# THE_FIRST.net
KiCad netlist of a schematic drawn in Altium Designer
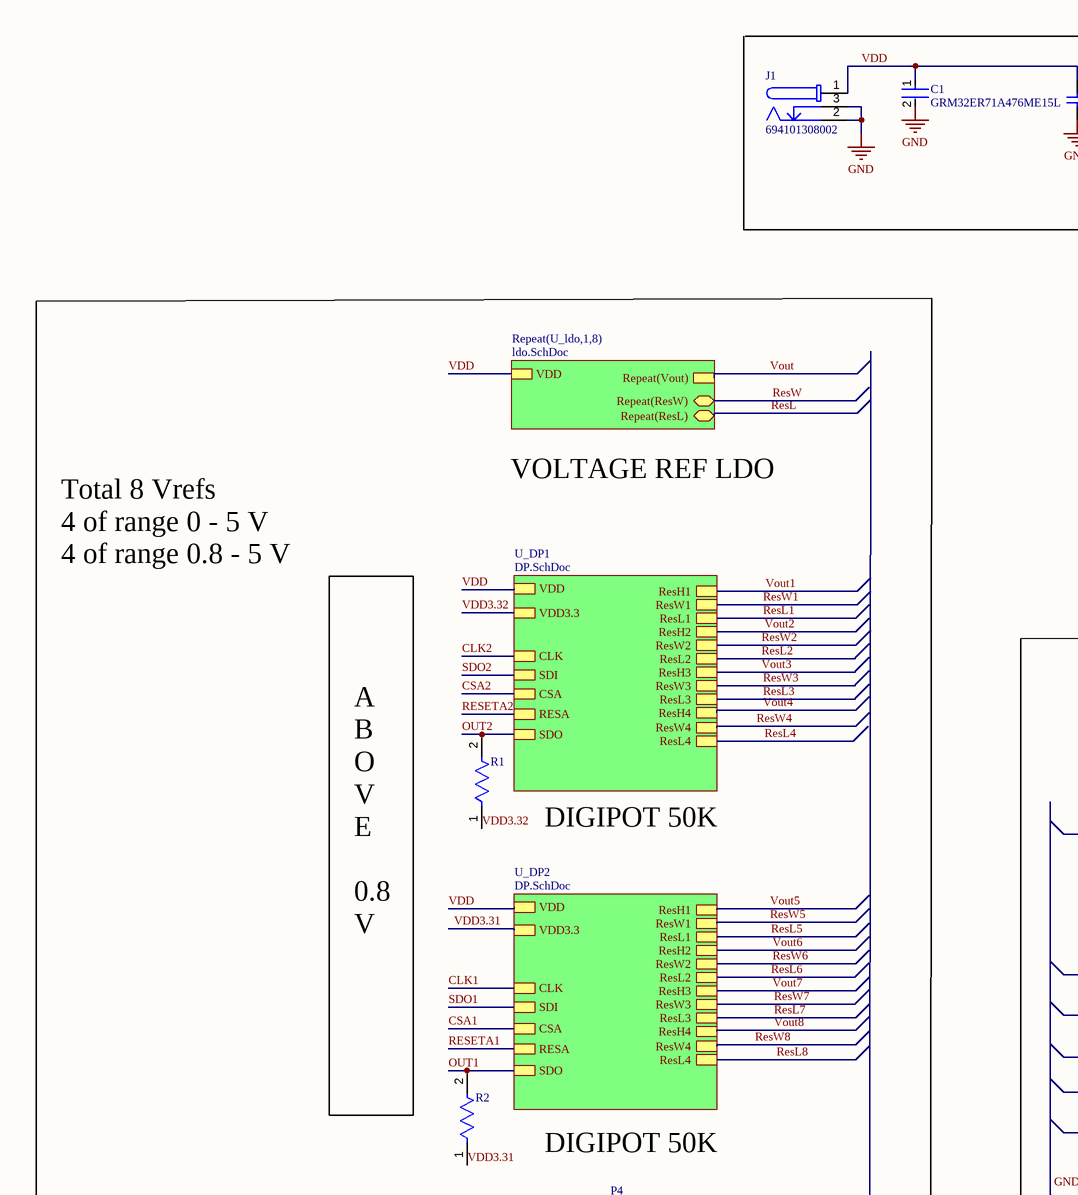
[diagram p0: THE_FIRST.SchDoc, top left]
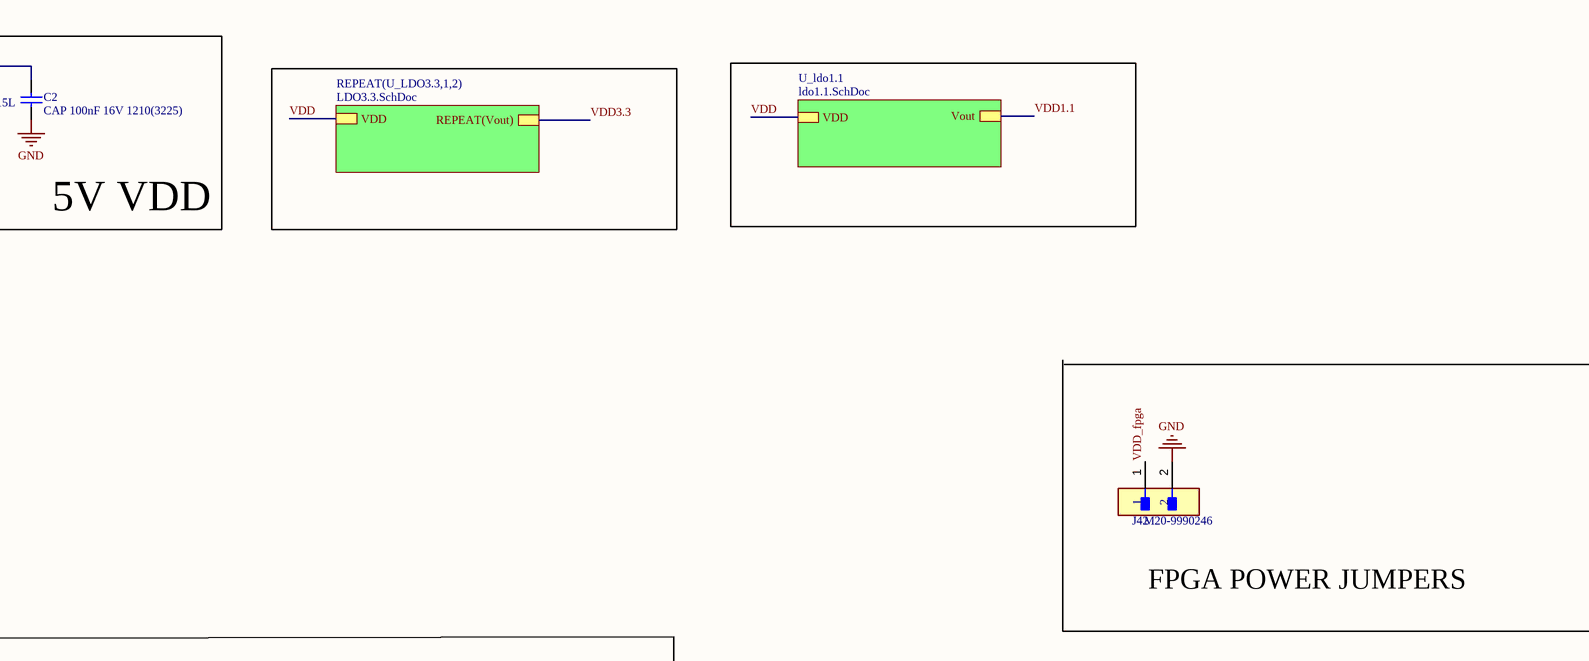
[diagram p1: THE_FIRST.SchDoc, top right]
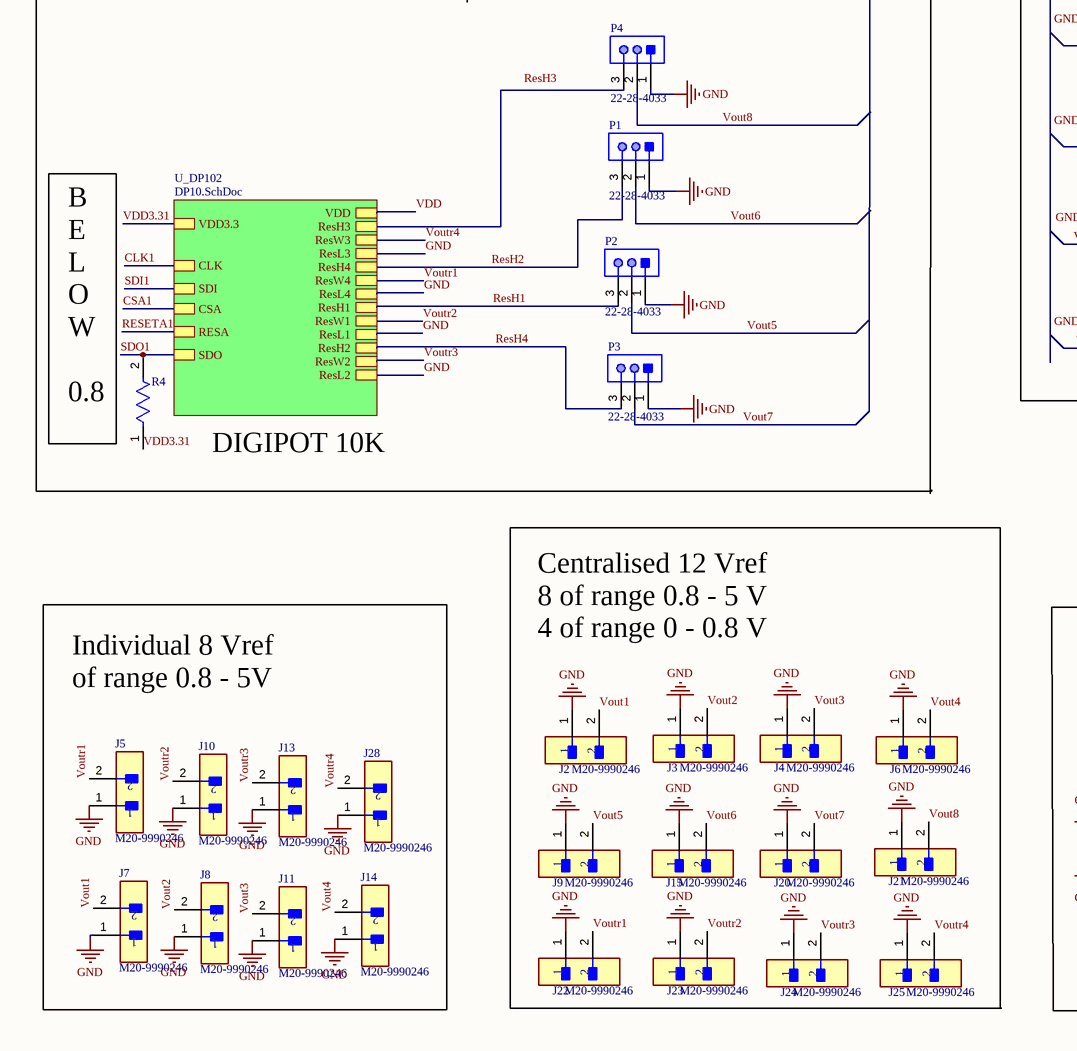
[diagram p2: THE_FIRST.SchDoc, bottom left]
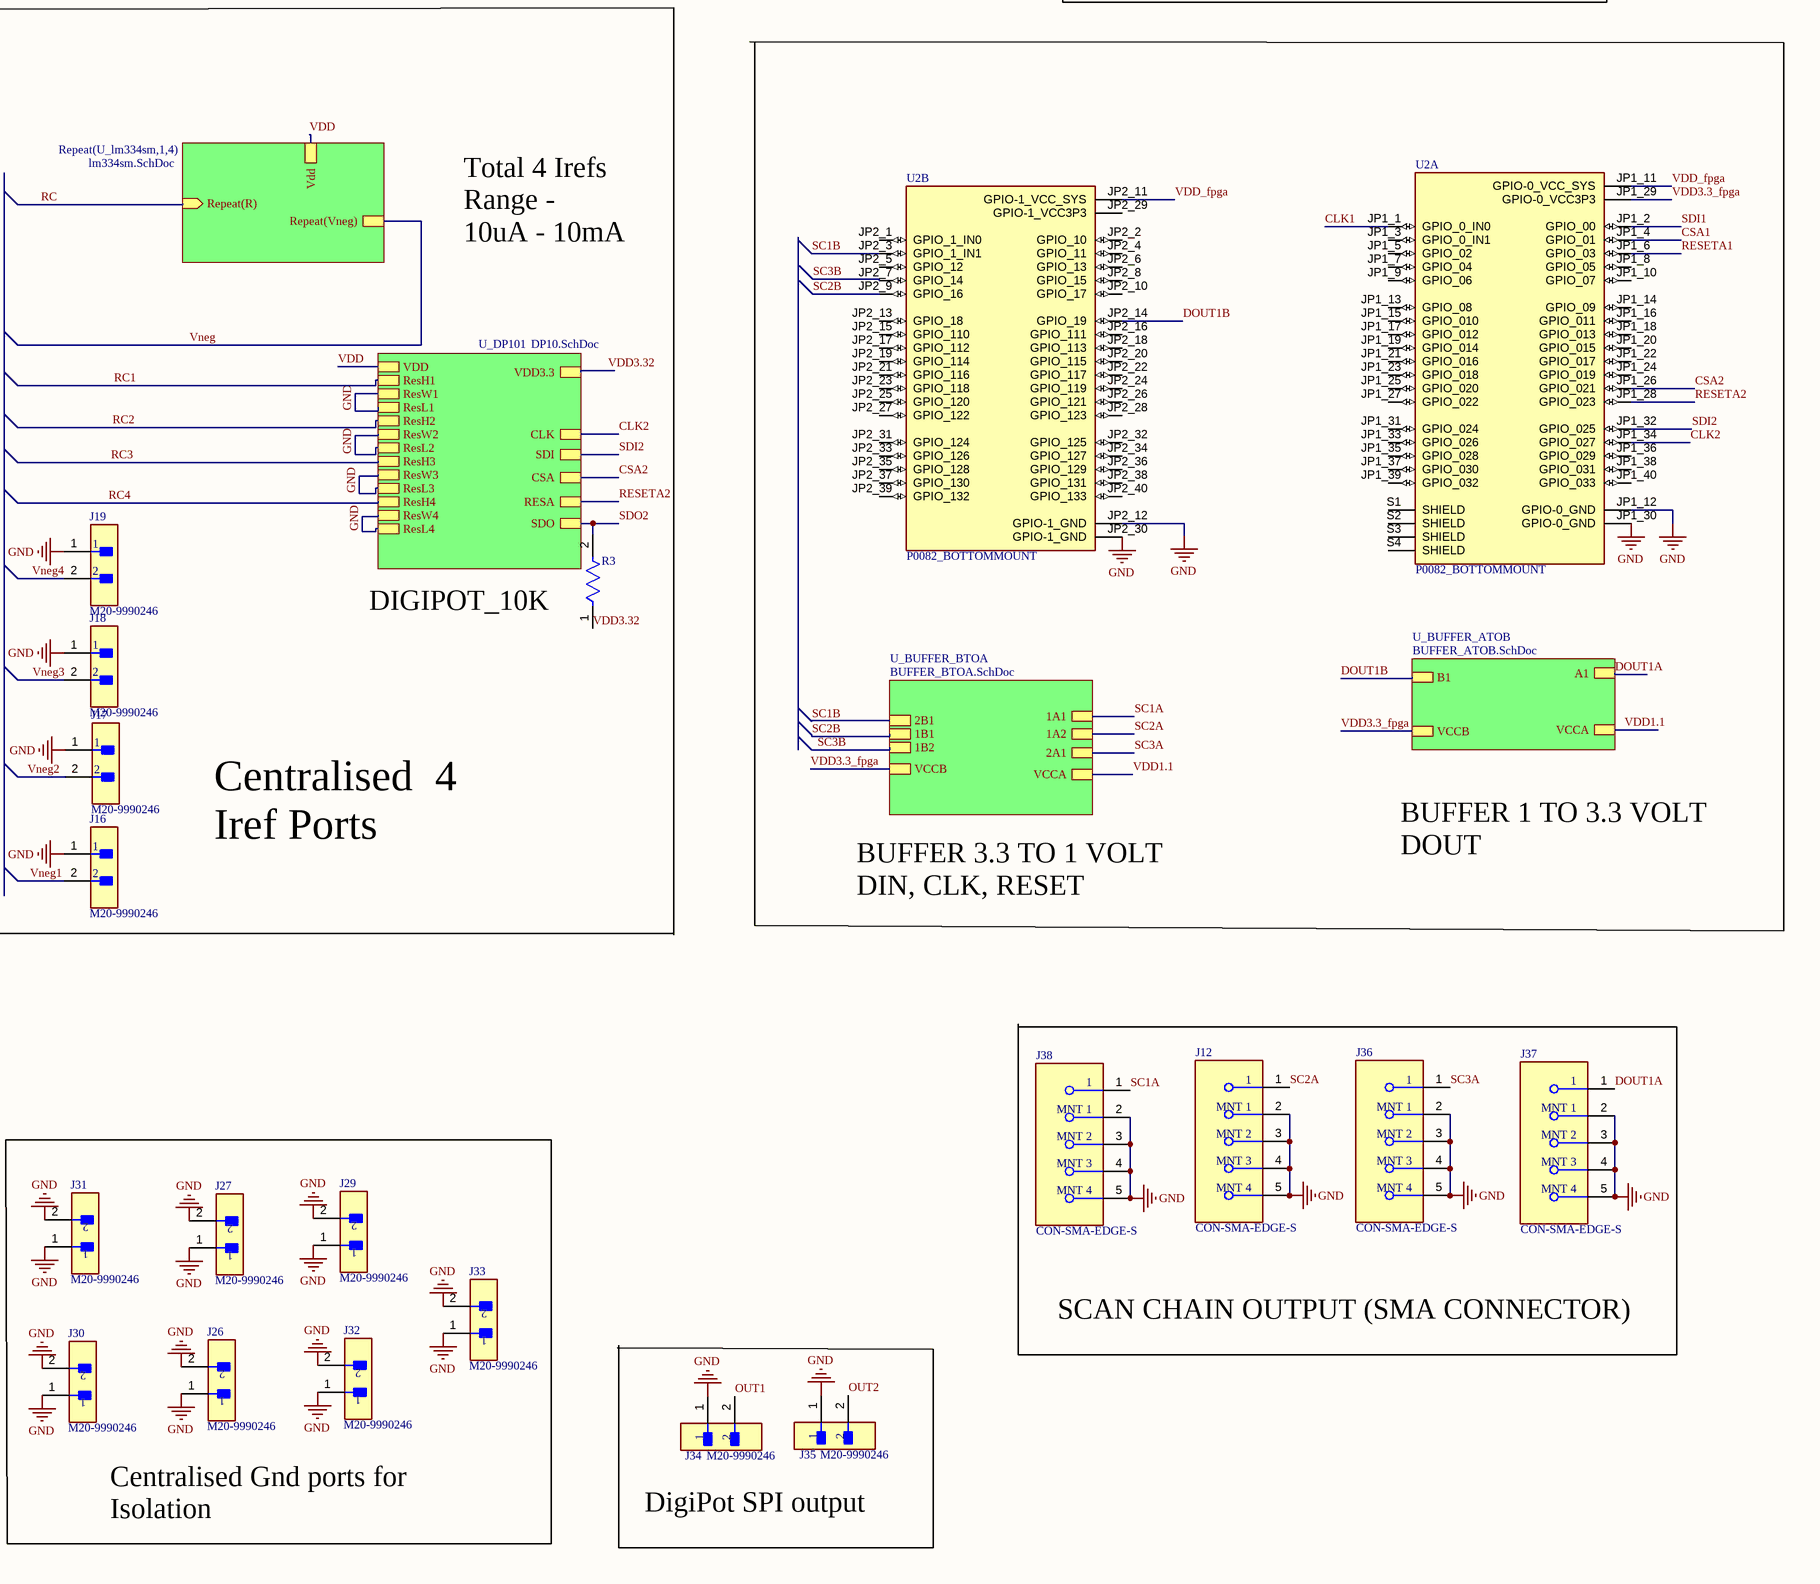
[diagram p3: THE_FIRST.SchDoc, bottom right]

(export (version "E")
  (design (tool "Eeschema 10.0.6"))
  (components
    (comp (ref "C1")
      (value "GRM32ER71A476ME15L")
      (footprint "FP-GRM32E-0_3-0_2-IPC_A")
      (description "Chip Multilayer Ceramic Capacitors for General Purpose, 1210, 47uF, X7R, 15%, 20%, 10V")
      (fields (field (name "VOLTAGE") "10V") (field (name "TOLERANCE") "20%"))
      (libsource (lib "Altium Content Vault") (part "02cd4be3c70576c341d710602a673aa"))
    )
    (comp (ref "C2")
      (value "CAP 100nF 16V 1210(3225)")
      (footprint "CAPC1210(3225)115_M")
      (description "CAP 100nF 16V ±1% 1210 (3225 Metric) Thickness 1.1mm SMD")
      (fields (field (name "TOLERANCE") "Â±1%") (field (name "MANUFACTURER") "Panasonic"))
      (libsource (lib "Altium Content Vault") (part "CAP"))
    )
    (comp (ref "J1")
      (value "694101308002")
      (footprint "694101308002")
      (libsource (lib "Altium Content Vault") (part "DC Power Jack"))
    )
    (comp (ref "J2")
      (value "M20-9990246")
      (footprint "FP-M20-9990246-MFG")
      (description "CONN HEADER VERT 2POS 2.54MM")
      (fields
        (field (name "OCTOPART") "https://octopart.com/m20-9990246-harwin-2590635")
        (field (name "MANUFACTURER") "Harwin")
      )
      (libsource (lib "Altium Content Vault") (part "3bc925449376181038e59eaffc5286c"))
    )
    (comp (ref "J3")
      (value "M20-9990246")
      (footprint "FP-M20-9990246-MFG")
      (description "CONN HEADER VERT 2POS 2.54MM")
      (fields
        (field (name "OCTOPART") "https://octopart.com/m20-9990246-harwin-2590635")
        (field (name "MANUFACTURER") "Harwin")
      )
      (libsource (lib "Altium Content Vault") (part "3bc925449376181038e59eaffc5286c"))
    )
    (comp (ref "J4")
      (value "M20-9990246")
      (footprint "FP-M20-9990246-MFG")
      (description "CONN HEADER VERT 2POS 2.54MM")
      (fields
        (field (name "OCTOPART") "https://octopart.com/m20-9990246-harwin-2590635")
        (field (name "MANUFACTURER") "Harwin")
      )
      (libsource (lib "Altium Content Vault") (part "3bc925449376181038e59eaffc5286c"))
    )
    (comp (ref "J5")
      (value "M20-9990246")
      (footprint "FP-M20-9990246-MFG")
      (description "CONN HEADER VERT 2POS 2.54MM")
      (fields
        (field (name "OCTOPART") "https://octopart.com/m20-9990246-harwin-2590635")
        (field (name "MANUFACTURER") "Harwin")
      )
      (libsource (lib "") (part "3bc925449376181038e59eaffc5286c_1"))
    )
    (comp (ref "J6")
      (value "M20-9990246")
      (footprint "FP-M20-9990246-MFG")
      (description "CONN HEADER VERT 2POS 2.54MM")
      (fields
        (field (name "OCTOPART") "https://octopart.com/m20-9990246-harwin-2590635")
        (field (name "MANUFACTURER") "Harwin")
      )
      (libsource (lib "Altium Content Vault") (part "3bc925449376181038e59eaffc5286c"))
    )
    (comp (ref "J7")
      (value "M20-9990246")
      (footprint "FP-M20-9990246-MFG")
      (description "CONN HEADER VERT 2POS 2.54MM")
      (fields
        (field (name "OCTOPART") "https://octopart.com/m20-9990246-harwin-2590635")
        (field (name "MANUFACTURER") "Harwin")
      )
      (libsource (lib "") (part "3bc925449376181038e59eaffc5286c_1"))
    )
    (comp (ref "J8")
      (value "M20-9990246")
      (footprint "FP-M20-9990246-MFG")
      (description "CONN HEADER VERT 2POS 2.54MM")
      (fields
        (field (name "OCTOPART") "https://octopart.com/m20-9990246-harwin-2590635")
        (field (name "MANUFACTURER") "Harwin")
      )
      (libsource (lib "") (part "3bc925449376181038e59eaffc5286c_1"))
    )
    (comp (ref "J9")
      (value "M20-9990246")
      (footprint "FP-M20-9990246-MFG")
      (description "CONN HEADER VERT 2POS 2.54MM")
      (fields
        (field (name "OCTOPART") "https://octopart.com/m20-9990246-harwin-2590635")
        (field (name "MANUFACTURER") "Harwin")
      )
      (libsource (lib "Altium Content Vault") (part "3bc925449376181038e59eaffc5286c"))
    )
    (comp (ref "J10")
      (value "M20-9990246")
      (footprint "FP-M20-9990246-MFG")
      (description "CONN HEADER VERT 2POS 2.54MM")
      (fields
        (field (name "OCTOPART") "https://octopart.com/m20-9990246-harwin-2590635")
        (field (name "MANUFACTURER") "Harwin")
      )
      (libsource (lib "") (part "3bc925449376181038e59eaffc5286c_1"))
    )
    (comp (ref "J11")
      (value "M20-9990246")
      (footprint "FP-M20-9990246-MFG")
      (description "CONN HEADER VERT 2POS 2.54MM")
      (fields
        (field (name "OCTOPART") "https://octopart.com/m20-9990246-harwin-2590635")
        (field (name "MANUFACTURER") "Harwin")
      )
      (libsource (lib "") (part "3bc925449376181038e59eaffc5286c_1"))
    )
    (comp (ref "J12")
      (value "CON-SMA-EDGE-S")
      (footprint "FP-CON-SMA-EDGE-S-MFG")
      (description "CONN SMA JACK STR EDGE MNT")
      (fields
        (field (name "OCTOPART") "https://octopart.com/con-sma-edge-s-rf+solutions-70967450")
        (field (name "MANUFACTURER") "RF Solutions Ltd.")
      )
      (libsource (lib "Altium Content Vault") (part "a163d97a771fcdd2fd1f1a9264c171f"))
    )
    (comp (ref "J13")
      (value "M20-9990246")
      (footprint "FP-M20-9990246-MFG")
      (description "CONN HEADER VERT 2POS 2.54MM")
      (fields
        (field (name "OCTOPART") "https://octopart.com/m20-9990246-harwin-2590635")
        (field (name "MANUFACTURER") "Harwin")
      )
      (libsource (lib "") (part "3bc925449376181038e59eaffc5286c_1"))
    )
    (comp (ref "J14")
      (value "M20-9990246")
      (footprint "FP-M20-9990246-MFG")
      (description "CONN HEADER VERT 2POS 2.54MM")
      (fields
        (field (name "OCTOPART") "https://octopart.com/m20-9990246-harwin-2590635")
        (field (name "MANUFACTURER") "Harwin")
      )
      (libsource (lib "") (part "3bc925449376181038e59eaffc5286c_1"))
    )
    (comp (ref "J15")
      (value "M20-9990246")
      (footprint "FP-M20-9990246-MFG")
      (description "CONN HEADER VERT 2POS 2.54MM")
      (fields
        (field (name "OCTOPART") "https://octopart.com/m20-9990246-harwin-2590635")
        (field (name "MANUFACTURER") "Harwin")
      )
      (libsource (lib "Altium Content Vault") (part "3bc925449376181038e59eaffc5286c"))
    )
    (comp (ref "J16")
      (value "M20-9990246")
      (footprint "FP-M20-9990246-MFG")
      (description "CONN HEADER VERT 2POS 2.54MM")
      (fields
        (field (name "OCTOPART") "https://octopart.com/m20-9990246-harwin-2590635")
        (field (name "MANUFACTURER") "Harwin")
      )
      (libsource (lib "") (part "3bc925449376181038e59eaffc5286c_2"))
    )
    (comp (ref "J17")
      (value "M20-9990246")
      (footprint "FP-M20-9990246-MFG")
      (description "CONN HEADER VERT 2POS 2.54MM")
      (fields
        (field (name "OCTOPART") "https://octopart.com/m20-9990246-harwin-2590635")
        (field (name "MANUFACTURER") "Harwin")
      )
      (libsource (lib "") (part "3bc925449376181038e59eaffc5286c_2"))
    )
    (comp (ref "J18")
      (value "M20-9990246")
      (footprint "FP-M20-9990246-MFG")
      (description "CONN HEADER VERT 2POS 2.54MM")
      (fields
        (field (name "OCTOPART") "https://octopart.com/m20-9990246-harwin-2590635")
        (field (name "MANUFACTURER") "Harwin")
      )
      (libsource (lib "") (part "3bc925449376181038e59eaffc5286c_2"))
    )
    (comp (ref "J19")
      (value "M20-9990246")
      (footprint "FP-M20-9990246-MFG")
      (description "CONN HEADER VERT 2POS 2.54MM")
      (fields
        (field (name "OCTOPART") "https://octopart.com/m20-9990246-harwin-2590635")
        (field (name "MANUFACTURER") "Harwin")
      )
      (libsource (lib "") (part "3bc925449376181038e59eaffc5286c_2"))
    )
    (comp (ref "J20")
      (value "M20-9990246")
      (footprint "FP-M20-9990246-MFG")
      (description "CONN HEADER VERT 2POS 2.54MM")
      (fields
        (field (name "OCTOPART") "https://octopart.com/m20-9990246-harwin-2590635")
        (field (name "MANUFACTURER") "Harwin")
      )
      (libsource (lib "Altium Content Vault") (part "3bc925449376181038e59eaffc5286c"))
    )
    (comp (ref "J21")
      (value "M20-9990246")
      (footprint "FP-M20-9990246-MFG")
      (description "CONN HEADER VERT 2POS 2.54MM")
      (fields
        (field (name "OCTOPART") "https://octopart.com/m20-9990246-harwin-2590635")
        (field (name "MANUFACTURER") "Harwin")
      )
      (libsource (lib "Altium Content Vault") (part "3bc925449376181038e59eaffc5286c"))
    )
    (comp (ref "J22")
      (value "M20-9990246")
      (footprint "FP-M20-9990246-MFG")
      (description "CONN HEADER VERT 2POS 2.54MM")
      (fields
        (field (name "OCTOPART") "https://octopart.com/m20-9990246-harwin-2590635")
        (field (name "MANUFACTURER") "Harwin")
      )
      (libsource (lib "Altium Content Vault") (part "3bc925449376181038e59eaffc5286c"))
    )
    (comp (ref "J23")
      (value "M20-9990246")
      (footprint "FP-M20-9990246-MFG")
      (description "CONN HEADER VERT 2POS 2.54MM")
      (fields
        (field (name "OCTOPART") "https://octopart.com/m20-9990246-harwin-2590635")
        (field (name "MANUFACTURER") "Harwin")
      )
      (libsource (lib "Altium Content Vault") (part "3bc925449376181038e59eaffc5286c"))
    )
    (comp (ref "J24")
      (value "M20-9990246")
      (footprint "FP-M20-9990246-MFG")
      (description "CONN HEADER VERT 2POS 2.54MM")
      (fields
        (field (name "OCTOPART") "https://octopart.com/m20-9990246-harwin-2590635")
        (field (name "MANUFACTURER") "Harwin")
      )
      (libsource (lib "Altium Content Vault") (part "3bc925449376181038e59eaffc5286c"))
    )
    (comp (ref "J25")
      (value "M20-9990246")
      (footprint "FP-M20-9990246-MFG")
      (description "CONN HEADER VERT 2POS 2.54MM")
      (fields
        (field (name "OCTOPART") "https://octopart.com/m20-9990246-harwin-2590635")
        (field (name "MANUFACTURER") "Harwin")
      )
      (libsource (lib "Altium Content Vault") (part "3bc925449376181038e59eaffc5286c"))
    )
    (comp (ref "J26")
      (value "M20-9990246")
      (footprint "FP-M20-9990246-MFG")
      (description "CONN HEADER VERT 2POS 2.54MM")
      (fields
        (field (name "OCTOPART") "https://octopart.com/m20-9990246-harwin-2590635")
        (field (name "MANUFACTURER") "Harwin")
      )
      (libsource (lib "") (part "3bc925449376181038e59eaffc5286c_1"))
    )
    (comp (ref "J27")
      (value "M20-9990246")
      (footprint "FP-M20-9990246-MFG")
      (description "CONN HEADER VERT 2POS 2.54MM")
      (fields
        (field (name "OCTOPART") "https://octopart.com/m20-9990246-harwin-2590635")
        (field (name "MANUFACTURER") "Harwin")
      )
      (libsource (lib "") (part "3bc925449376181038e59eaffc5286c_1"))
    )
    (comp (ref "J28")
      (value "M20-9990246")
      (footprint "FP-M20-9990246-MFG")
      (description "CONN HEADER VERT 2POS 2.54MM")
      (fields
        (field (name "OCTOPART") "https://octopart.com/m20-9990246-harwin-2590635")
        (field (name "MANUFACTURER") "Harwin")
      )
      (libsource (lib "") (part "3bc925449376181038e59eaffc5286c_1"))
    )
    (comp (ref "J29")
      (value "M20-9990246")
      (footprint "FP-M20-9990246-MFG")
      (description "CONN HEADER VERT 2POS 2.54MM")
      (fields
        (field (name "OCTOPART") "https://octopart.com/m20-9990246-harwin-2590635")
        (field (name "MANUFACTURER") "Harwin")
      )
      (libsource (lib "") (part "3bc925449376181038e59eaffc5286c_1"))
    )
    (comp (ref "J30")
      (value "M20-9990246")
      (footprint "FP-M20-9990246-MFG")
      (description "CONN HEADER VERT 2POS 2.54MM")
      (fields
        (field (name "OCTOPART") "https://octopart.com/m20-9990246-harwin-2590635")
        (field (name "MANUFACTURER") "Harwin")
      )
      (libsource (lib "") (part "3bc925449376181038e59eaffc5286c_1"))
    )
    (comp (ref "J31")
      (value "M20-9990246")
      (footprint "FP-M20-9990246-MFG")
      (description "CONN HEADER VERT 2POS 2.54MM")
      (fields
        (field (name "OCTOPART") "https://octopart.com/m20-9990246-harwin-2590635")
        (field (name "MANUFACTURER") "Harwin")
      )
      (libsource (lib "") (part "3bc925449376181038e59eaffc5286c_1"))
    )
    (comp (ref "J32")
      (value "M20-9990246")
      (footprint "FP-M20-9990246-MFG")
      (description "CONN HEADER VERT 2POS 2.54MM")
      (fields
        (field (name "OCTOPART") "https://octopart.com/m20-9990246-harwin-2590635")
        (field (name "MANUFACTURER") "Harwin")
      )
      (libsource (lib "") (part "3bc925449376181038e59eaffc5286c_1"))
    )
    (comp (ref "J33")
      (value "M20-9990246")
      (footprint "FP-M20-9990246-MFG")
      (description "CONN HEADER VERT 2POS 2.54MM")
      (fields
        (field (name "OCTOPART") "https://octopart.com/m20-9990246-harwin-2590635")
        (field (name "MANUFACTURER") "Harwin")
      )
      (libsource (lib "") (part "3bc925449376181038e59eaffc5286c_1"))
    )
    (comp (ref "J34")
      (value "M20-9990246")
      (footprint "FP-M20-9990246-MFG")
      (description "CONN HEADER VERT 2POS 2.54MM")
      (fields
        (field (name "OCTOPART") "https://octopart.com/m20-9990246-harwin-2590635")
        (field (name "MANUFACTURER") "Harwin")
      )
      (libsource (lib "Altium Content Vault") (part "3bc925449376181038e59eaffc5286c"))
    )
    (comp (ref "J35")
      (value "M20-9990246")
      (footprint "FP-M20-9990246-MFG")
      (description "CONN HEADER VERT 2POS 2.54MM")
      (fields
        (field (name "OCTOPART") "https://octopart.com/m20-9990246-harwin-2590635")
        (field (name "MANUFACTURER") "Harwin")
      )
      (libsource (lib "Altium Content Vault") (part "3bc925449376181038e59eaffc5286c"))
    )
    (comp (ref "J36")
      (value "CON-SMA-EDGE-S")
      (footprint "FP-CON-SMA-EDGE-S-MFG")
      (description "CONN SMA JACK STR EDGE MNT")
      (fields
        (field (name "OCTOPART") "https://octopart.com/con-sma-edge-s-rf+solutions-70967450")
        (field (name "MANUFACTURER") "RF Solutions Ltd.")
      )
      (libsource (lib "Altium Content Vault") (part "a163d97a771fcdd2fd1f1a9264c171f"))
    )
    (comp (ref "J37")
      (value "CON-SMA-EDGE-S")
      (footprint "FP-CON-SMA-EDGE-S-MFG")
      (description "CONN SMA JACK STR EDGE MNT")
      (fields
        (field (name "OCTOPART") "https://octopart.com/con-sma-edge-s-rf+solutions-70967450")
        (field (name "MANUFACTURER") "RF Solutions Ltd.")
      )
      (libsource (lib "Altium Content Vault") (part "a163d97a771fcdd2fd1f1a9264c171f"))
    )
    (comp (ref "J38")
      (value "CON-SMA-EDGE-S")
      (footprint "FP-CON-SMA-EDGE-S-MFG")
      (description "CONN SMA JACK STR EDGE MNT")
      (fields
        (field (name "OCTOPART") "https://octopart.com/con-sma-edge-s-rf+solutions-70967450")
        (field (name "MANUFACTURER") "RF Solutions Ltd.")
      )
      (libsource (lib "Altium Content Vault") (part "a163d97a771fcdd2fd1f1a9264c171f"))
    )
    (comp (ref "J42")
      (value "M20-9990246")
      (footprint "FP-M20-9990246-MFG")
      (description "CONN HEADER VERT 2POS 2.54MM")
      (fields
        (field (name "OCTOPART") "https://octopart.com/m20-9990246-harwin-2590635")
        (field (name "MANUFACTURER") "Harwin")
      )
      (libsource (lib "Altium Content Vault") (part "3bc925449376181038e59eaffc5286c"))
    )
    (comp (ref "P1")
      (value "22-28-4033")
      (footprint "MOLX-22-28-4033_V")
      (description "Male Header, Pitch 2.54 mm, 1 x 3 Position, Height 8.38 mm, Tail Length 3.18 mm, RoHS, Bulk")
      (fields (field (name "MANUFACTURER") "Molex"))
      (libsource (lib "Altium Content Vault") (part "CN-1P-M-R3"))
    )
    (comp (ref "P2")
      (value "22-28-4033")
      (footprint "MOLX-22-28-4033_V")
      (description "Male Header, Pitch 2.54 mm, 1 x 3 Position, Height 8.38 mm, Tail Length 3.18 mm, RoHS, Bulk")
      (fields (field (name "MANUFACTURER") "Molex"))
      (libsource (lib "Altium Content Vault") (part "CN-1P-M-R3"))
    )
    (comp (ref "P3")
      (value "22-28-4033")
      (footprint "MOLX-22-28-4033_V")
      (description "Male Header, Pitch 2.54 mm, 1 x 3 Position, Height 8.38 mm, Tail Length 3.18 mm, RoHS, Bulk")
      (fields (field (name "MANUFACTURER") "Molex"))
      (libsource (lib "Altium Content Vault") (part "CN-1P-M-R3"))
    )
    (comp (ref "P4")
      (value "22-28-4033")
      (footprint "MOLX-22-28-4033_V")
      (description "Male Header, Pitch 2.54 mm, 1 x 3 Position, Height 8.38 mm, Tail Length 3.18 mm, RoHS, Bulk")
      (fields (field (name "MANUFACTURER") "Molex"))
      (libsource (lib "Altium Content Vault") (part "CN-1P-M-R3"))
    )
    (comp (ref "R1")
      (value "ERA-2AEB222X")
      (footprint "FP-ERA2A-MFG")
      (description "RES SMD 2.2K OHM 0.1% 1/16W 0402")
      (fields
        (field (name "TOLERANCE") "0.1%")
        (field (name "OCTOPART") "https://octopart.com/era-2aeb222x-panasonic-9251391")
      )
      (libsource (lib "Altium Content Vault") (part "1029c3af85768c4190bb7ad29bc67b5"))
    )
    (comp (ref "R2")
      (value "ERA-2AEB222X")
      (footprint "FP-ERA2A-MFG")
      (description "RES SMD 2.2K OHM 0.1% 1/16W 0402")
      (fields
        (field (name "TOLERANCE") "0.1%")
        (field (name "OCTOPART") "https://octopart.com/era-2aeb222x-panasonic-9251391")
      )
      (libsource (lib "Altium Content Vault") (part "1029c3af85768c4190bb7ad29bc67b5"))
    )
    (comp (ref "R3")
      (value "ERA-2AEB222X")
      (footprint "FP-ERA2A-MFG")
      (description "RES SMD 2.2K OHM 0.1% 1/16W 0402")
      (fields
        (field (name "TOLERANCE") "0.1%")
        (field (name "OCTOPART") "https://octopart.com/era-2aeb222x-panasonic-9251391")
      )
      (libsource (lib "Altium Content Vault") (part "1029c3af85768c4190bb7ad29bc67b5"))
    )
    (comp (ref "R4")
      (value "ERA-2AEB222X")
      (footprint "FP-ERA2A-MFG")
      (description "RES SMD 2.2K OHM 0.1% 1/16W 0402")
      (fields
        (field (name "TOLERANCE") "0.1%")
        (field (name "OCTOPART") "https://octopart.com/era-2aeb222x-panasonic-9251391")
      )
      (libsource (lib "Altium Content Vault") (part "1029c3af85768c4190bb7ad29bc67b5"))
    )
    (comp (ref "U2")
      (value "P0082_BOTTOMMOUNT")
      (footprint "MODULE_P0082_BOTTOMMOUNT")
      (description "Cyclone IV E FPGA DE0-Nano EP4CE22 CycloneÂ® IV E FPGA Evaluation Board")
      (fields (field (name "MF") "Terasic Inc.") (field (name "MP") "P0082"))
      (libsource (lib "P0082_BOTTOMMOUNT") (part "P0082_BOTTOMMOUNT"))
    )
  )
  (nets
    (net (code "1") (name "/CLK1") (class "Default")
      (node (ref "U2") (pin "JP1_1") (pinfunction "GPIO_0_IN0_JP1_1") (pintype "bidirectional"))
    )
    (net (code "2") (name "/CLK2") (class "Default")
      (node (ref "U2") (pin "JP1_34") (pinfunction "GPIO_027_JP1_34") (pintype "bidirectional"))
    )
    (net (code "3") (name "/CSA1") (class "Default")
      (node (ref "U2") (pin "JP1_4") (pinfunction "GPIO_01_JP1_4") (pintype "bidirectional"))
    )
    (net (code "4") (name "/CSA2") (class "Default")
      (node (ref "U2") (pin "JP1_26") (pinfunction "GPIO_021_JP1_26") (pintype "bidirectional"))
    )
    (net (code "5") (name "/DOUT1A") (class "Default")
      (node (ref "J37") (pin "1") (pinfunction "1_1") (pintype "passive"))
    )
    (net (code "6") (name "/DOUT1B") (class "Default")
      (node (ref "U2") (pin "JP2_14") (pinfunction "GPIO_19_JP2_14") (pintype "bidirectional"))
    )
    (net (code "7") (name "/OUT1") (class "Default")
      (node (ref "J34") (pin "2") (pinfunction "2_2") (pintype "passive"))
      (node (ref "R2") (pin "2") (pinfunction "2_2") (pintype "passive"))
    )
    (net (code "8") (name "/OUT2") (class "Default")
      (node (ref "J35") (pin "2") (pinfunction "2_2") (pintype "passive"))
      (node (ref "R1") (pin "2") (pinfunction "2_2") (pintype "passive"))
    )
    (net (code "14") (name "/RESETA1") (class "Default")
      (node (ref "U2") (pin "JP1_6") (pinfunction "GPIO_03_JP1_6") (pintype "bidirectional"))
    )
    (net (code "15") (name "/RESETA2") (class "Default")
      (node (ref "U2") (pin "JP1_28") (pinfunction "GPIO_023_JP1_28") (pintype "bidirectional"))
    )
    (net (code "16") (name "/ResH1") (class "Default")
      (node (ref "P2") (pin "3") (pinfunction "3_3") (pintype "passive"))
    )
    (net (code "17") (name "/ResH2") (class "Default")
      (node (ref "P1") (pin "3") (pinfunction "3_3") (pintype "passive"))
    )
    (net (code "19") (name "/ResH3_1") (class "Default")
      (node (ref "P4") (pin "3") (pinfunction "3_3") (pintype "passive"))
    )
    (net (code "20") (name "/ResH4") (class "Default")
      (node (ref "P3") (pin "3") (pinfunction "3_3") (pintype "passive"))
    )
    (net (code "39") (name "/SC1A") (class "Default")
      (node (ref "J38") (pin "1") (pinfunction "1_1") (pintype "passive"))
    )
    (net (code "40") (name "/SC1B") (class "Default")
      (node (ref "U2") (pin "JP2_3") (pinfunction "GPIO_1_IN1_JP2_3") (pintype "bidirectional"))
    )
    (net (code "41") (name "/SC2A") (class "Default")
      (node (ref "J12") (pin "1") (pinfunction "1_1") (pintype "passive"))
    )
    (net (code "42") (name "/SC2B") (class "Default")
      (node (ref "U2") (pin "JP2_9") (pinfunction "GPIO_16_JP2_9") (pintype "bidirectional"))
    )
    (net (code "43") (name "/SC3A") (class "Default")
      (node (ref "J36") (pin "1") (pinfunction "1_1") (pintype "passive"))
    )
    (net (code "44") (name "/SC3B") (class "Default")
      (node (ref "U2") (pin "JP2_7") (pinfunction "GPIO_14_JP2_7") (pintype "bidirectional"))
    )
    (net (code "45") (name "/SDI1") (class "Default")
      (node (ref "U2") (pin "JP1_2") (pinfunction "GPIO_00_JP1_2") (pintype "bidirectional"))
    )
    (net (code "46") (name "/SDI2") (class "Default")
      (node (ref "U2") (pin "JP1_32") (pinfunction "GPIO_025_JP1_32") (pintype "bidirectional"))
    )
    (net (code "47") (name "/SDO1") (class "Default")
      (node (ref "R4") (pin "2") (pinfunction "2_2") (pintype "passive"))
    )
    (net (code "48") (name "/SDO2") (class "Default")
      (node (ref "R3") (pin "2") (pinfunction "2_2") (pintype "passive"))
    )
    (net (code "49") (name "/VDD") (class "Default")
      (node (ref "C1") (pin "1") (pinfunction "1_1") (pintype "passive"))
      (node (ref "C2") (pin "2") (pinfunction "2_2") (pintype "passive"))
      (node (ref "J1") (pin "1") (pinfunction "1_1") (pintype "passive"))
    )
    (net (code "52") (name "/VDD3.3_fpga") (class "Default")
      (node (ref "U2") (pin "JP1_29") (pinfunction "GPIO-0_VCC3P3_JP1_29") (pintype "power_in"))
    )
    (net (code "53") (name "/VDD3.31") (class "Default")
      (node (ref "R2") (pin "1") (pinfunction "1_1") (pintype "passive"))
      (node (ref "R4") (pin "1") (pinfunction "1_1") (pintype "passive"))
    )
    (net (code "54") (name "/VDD3.32") (class "Default")
      (node (ref "R1") (pin "1") (pinfunction "1_1") (pintype "passive"))
      (node (ref "R3") (pin "1") (pinfunction "1_1") (pintype "passive"))
    )
    (net (code "55") (name "/VDD_fpga") (class "Default")
      (node (ref "J42") (pin "1") (pinfunction "1_1") (pintype "passive"))
      (node (ref "U2") (pin "JP1_11") (pinfunction "GPIO-0_VCC_SYS_JP1_11") (pintype "power_in"))
      (node (ref "U2") (pin "JP2_11") (pinfunction "GPIO-1_VCC_SYS_JP2_11") (pintype "power_in"))
    )
    (net (code "57") (name "/Vneg1") (class "Default")
      (node (ref "J16") (pin "2") (pinfunction "2_2") (pintype "passive"))
    )
    (net (code "58") (name "/Vneg2") (class "Default")
      (node (ref "J17") (pin "2") (pinfunction "2_2") (pintype "passive"))
    )
    (net (code "59") (name "/Vneg3") (class "Default")
      (node (ref "J18") (pin "2") (pinfunction "2_2") (pintype "passive"))
    )
    (net (code "60") (name "/Vneg4") (class "Default")
      (node (ref "J19") (pin "2") (pinfunction "2_2") (pintype "passive"))
    )
    (net (code "62") (name "/Vout1") (class "Default")
      (node (ref "J2") (pin "2") (pinfunction "2_2") (pintype "passive"))
      (node (ref "J7") (pin "2") (pinfunction "2_2") (pintype "passive"))
    )
    (net (code "63") (name "/Vout2") (class "Default")
      (node (ref "J3") (pin "2") (pinfunction "2_2") (pintype "passive"))
      (node (ref "J8") (pin "2") (pinfunction "2_2") (pintype "passive"))
    )
    (net (code "64") (name "/Vout3") (class "Default")
      (node (ref "J11") (pin "2") (pinfunction "2_2") (pintype "passive"))
      (node (ref "J4") (pin "2") (pinfunction "2_2") (pintype "passive"))
    )
    (net (code "65") (name "/Vout4") (class "Default")
      (node (ref "J14") (pin "2") (pinfunction "2_2") (pintype "passive"))
      (node (ref "J6") (pin "2") (pinfunction "2_2") (pintype "passive"))
    )
    (net (code "66") (name "/Vout5") (class "Default")
      (node (ref "J9") (pin "2") (pinfunction "2_2") (pintype "passive"))
      (node (ref "P2") (pin "2") (pinfunction "2_2") (pintype "passive"))
    )
    (net (code "67") (name "/Vout6") (class "Default")
      (node (ref "J15") (pin "2") (pinfunction "2_2") (pintype "passive"))
      (node (ref "P1") (pin "2") (pinfunction "2_2") (pintype "passive"))
    )
    (net (code "68") (name "/Vout7") (class "Default")
      (node (ref "J20") (pin "2") (pinfunction "2_2") (pintype "passive"))
      (node (ref "P3") (pin "2") (pinfunction "2_2") (pintype "passive"))
    )
    (net (code "69") (name "/Vout8") (class "Default")
      (node (ref "J21") (pin "2") (pinfunction "2_2") (pintype "passive"))
      (node (ref "P4") (pin "2") (pinfunction "2_2") (pintype "passive"))
    )
    (net (code "70") (name "/Voutr1") (class "Default")
      (node (ref "J22") (pin "2") (pinfunction "2_2") (pintype "passive"))
      (node (ref "J5") (pin "2") (pinfunction "2_2") (pintype "passive"))
    )
    (net (code "71") (name "/Voutr2") (class "Default")
      (node (ref "J10") (pin "2") (pinfunction "2_2") (pintype "passive"))
      (node (ref "J23") (pin "2") (pinfunction "2_2") (pintype "passive"))
    )
    (net (code "72") (name "/Voutr3") (class "Default")
      (node (ref "J13") (pin "2") (pinfunction "2_2") (pintype "passive"))
      (node (ref "J24") (pin "2") (pinfunction "2_2") (pintype "passive"))
    )
    (net (code "73") (name "/Voutr4") (class "Default")
      (node (ref "J25") (pin "2") (pinfunction "2_2") (pintype "passive"))
      (node (ref "J28") (pin "2") (pinfunction "2_2") (pintype "passive"))
    )
    (net (code "74") (name "GND") (class "Default")
      (node (ref "C1") (pin "2") (pinfunction "2_2") (pintype "passive"))
      (node (ref "C2") (pin "1") (pinfunction "1_1") (pintype "passive"))
      (node (ref "J1") (pin "2") (pinfunction "2_2") (pintype "passive"))
      (node (ref "J1") (pin "3") (pinfunction "3_3") (pintype "passive"))
      (node (ref "J10") (pin "1") (pinfunction "1_1") (pintype "passive"))
      (node (ref "J11") (pin "1") (pinfunction "1_1") (pintype "passive"))
      (node (ref "J12") (pin "2") (pinfunction "MNT_1_2") (pintype "passive"))
      (node (ref "J12") (pin "3") (pinfunction "MNT_2_3") (pintype "passive"))
      (node (ref "J12") (pin "4") (pinfunction "MNT_3_4") (pintype "passive"))
      (node (ref "J12") (pin "5") (pinfunction "MNT_4_5") (pintype "passive"))
      (node (ref "J13") (pin "1") (pinfunction "1_1") (pintype "passive"))
      (node (ref "J14") (pin "1") (pinfunction "1_1") (pintype "passive"))
      (node (ref "J15") (pin "1") (pinfunction "1_1") (pintype "passive"))
      (node (ref "J16") (pin "1") (pinfunction "1_1") (pintype "passive"))
      (node (ref "J17") (pin "1") (pinfunction "1_1") (pintype "passive"))
      (node (ref "J18") (pin "1") (pinfunction "1_1") (pintype "passive"))
      (node (ref "J19") (pin "1") (pinfunction "1_1") (pintype "passive"))
      (node (ref "J2") (pin "1") (pinfunction "1_1") (pintype "passive"))
      (node (ref "J20") (pin "1") (pinfunction "1_1") (pintype "passive"))
      (node (ref "J21") (pin "1") (pinfunction "1_1") (pintype "passive"))
      (node (ref "J22") (pin "1") (pinfunction "1_1") (pintype "passive"))
      (node (ref "J23") (pin "1") (pinfunction "1_1") (pintype "passive"))
      (node (ref "J24") (pin "1") (pinfunction "1_1") (pintype "passive"))
      (node (ref "J25") (pin "1") (pinfunction "1_1") (pintype "passive"))
      (node (ref "J26") (pin "1") (pinfunction "1_1") (pintype "passive"))
      (node (ref "J26") (pin "2") (pinfunction "2_2") (pintype "passive"))
      (node (ref "J27") (pin "1") (pinfunction "1_1") (pintype "passive"))
      (node (ref "J27") (pin "2") (pinfunction "2_2") (pintype "passive"))
      (node (ref "J28") (pin "1") (pinfunction "1_1") (pintype "passive"))
      (node (ref "J29") (pin "1") (pinfunction "1_1") (pintype "passive"))
      (node (ref "J29") (pin "2") (pinfunction "2_2") (pintype "passive"))
      (node (ref "J3") (pin "1") (pinfunction "1_1") (pintype "passive"))
      (node (ref "J30") (pin "1") (pinfunction "1_1") (pintype "passive"))
      (node (ref "J30") (pin "2") (pinfunction "2_2") (pintype "passive"))
      (node (ref "J31") (pin "1") (pinfunction "1_1") (pintype "passive"))
      (node (ref "J31") (pin "2") (pinfunction "2_2") (pintype "passive"))
      (node (ref "J32") (pin "1") (pinfunction "1_1") (pintype "passive"))
      (node (ref "J32") (pin "2") (pinfunction "2_2") (pintype "passive"))
      (node (ref "J33") (pin "1") (pinfunction "1_1") (pintype "passive"))
      (node (ref "J33") (pin "2") (pinfunction "2_2") (pintype "passive"))
      (node (ref "J34") (pin "1") (pinfunction "1_1") (pintype "passive"))
      (node (ref "J35") (pin "1") (pinfunction "1_1") (pintype "passive"))
      (node (ref "J36") (pin "2") (pinfunction "MNT_1_2") (pintype "passive"))
      (node (ref "J36") (pin "3") (pinfunction "MNT_2_3") (pintype "passive"))
      (node (ref "J36") (pin "4") (pinfunction "MNT_3_4") (pintype "passive"))
      (node (ref "J36") (pin "5") (pinfunction "MNT_4_5") (pintype "passive"))
      (node (ref "J37") (pin "2") (pinfunction "MNT_1_2") (pintype "passive"))
      (node (ref "J37") (pin "3") (pinfunction "MNT_2_3") (pintype "passive"))
      (node (ref "J37") (pin "4") (pinfunction "MNT_3_4") (pintype "passive"))
      (node (ref "J37") (pin "5") (pinfunction "MNT_4_5") (pintype "passive"))
      (node (ref "J38") (pin "2") (pinfunction "MNT_1_2") (pintype "passive"))
      (node (ref "J38") (pin "3") (pinfunction "MNT_2_3") (pintype "passive"))
      (node (ref "J38") (pin "4") (pinfunction "MNT_3_4") (pintype "passive"))
      (node (ref "J38") (pin "5") (pinfunction "MNT_4_5") (pintype "passive"))
      (node (ref "J4") (pin "1") (pinfunction "1_1") (pintype "passive"))
      (node (ref "J42") (pin "2") (pinfunction "2_2") (pintype "passive"))
      (node (ref "J5") (pin "1") (pinfunction "1_1") (pintype "passive"))
      (node (ref "J6") (pin "1") (pinfunction "1_1") (pintype "passive"))
      (node (ref "J7") (pin "1") (pinfunction "1_1") (pintype "passive"))
      (node (ref "J8") (pin "1") (pinfunction "1_1") (pintype "passive"))
      (node (ref "J9") (pin "1") (pinfunction "1_1") (pintype "passive"))
      (node (ref "P1") (pin "1") (pinfunction "1_1") (pintype "passive"))
      (node (ref "P2") (pin "1") (pinfunction "1_1") (pintype "passive"))
      (node (ref "P3") (pin "1") (pinfunction "1_1") (pintype "passive"))
      (node (ref "P4") (pin "1") (pinfunction "1_1") (pintype "passive"))
      (node (ref "U2") (pin "JP1_12") (pinfunction "GPIO-0_GND_JP1_12") (pintype "power_in"))
      (node (ref "U2") (pin "JP1_30") (pinfunction "GPIO-0_GND_JP1_30") (pintype "power_in"))
      (node (ref "U2") (pin "JP2_12") (pinfunction "GPIO-1_GND_JP2_12") (pintype "power_in"))
      (node (ref "U2") (pin "JP2_30") (pinfunction "GPIO-1_GND_JP2_30") (pintype "power_in"))
    )
    (net (code "75") (name "unconnected-(U2A-GPIO_0_IN1-PadJP1_3)") (class "Default")
      (node (ref "U2") (pin "JP1_3") (pinfunction "GPIO_0_IN1_JP1_3") (pintype "bidirectional"))
    )
    (net (code "76") (name "unconnected-(U2A-GPIO_02-PadJP1_5)") (class "Default")
      (node (ref "U2") (pin "JP1_5") (pinfunction "GPIO_02_JP1_5") (pintype "bidirectional"))
    )
    (net (code "77") (name "unconnected-(U2A-GPIO_04-PadJP1_7)") (class "Default")
      (node (ref "U2") (pin "JP1_7") (pinfunction "GPIO_04_JP1_7") (pintype "bidirectional"))
    )
    (net (code "78") (name "unconnected-(U2A-GPIO_05-PadJP1_8)") (class "Default")
      (node (ref "U2") (pin "JP1_8") (pinfunction "GPIO_05_JP1_8") (pintype "bidirectional"))
    )
    (net (code "79") (name "unconnected-(U2A-GPIO_06-PadJP1_9)") (class "Default")
      (node (ref "U2") (pin "JP1_9") (pinfunction "GPIO_06_JP1_9") (pintype "bidirectional"))
    )
    (net (code "80") (name "unconnected-(U2A-GPIO_07-PadJP1_10)") (class "Default")
      (node (ref "U2") (pin "JP1_10") (pinfunction "GPIO_07_JP1_10") (pintype "bidirectional"))
    )
    (net (code "81") (name "unconnected-(U2A-GPIO_08-PadJP1_13)") (class "Default")
      (node (ref "U2") (pin "JP1_13") (pinfunction "GPIO_08_JP1_13") (pintype "bidirectional"))
    )
    (net (code "82") (name "unconnected-(U2A-GPIO_09-PadJP1_14)") (class "Default")
      (node (ref "U2") (pin "JP1_14") (pinfunction "GPIO_09_JP1_14") (pintype "bidirectional"))
    )
    (net (code "83") (name "unconnected-(U2A-GPIO_010-PadJP1_15)") (class "Default")
      (node (ref "U2") (pin "JP1_15") (pinfunction "GPIO_010_JP1_15") (pintype "bidirectional"))
    )
    (net (code "84") (name "unconnected-(U2A-GPIO_011-PadJP1_16)") (class "Default")
      (node (ref "U2") (pin "JP1_16") (pinfunction "GPIO_011_JP1_16") (pintype "bidirectional"))
    )
    (net (code "85") (name "unconnected-(U2A-GPIO_012-PadJP1_17)") (class "Default")
      (node (ref "U2") (pin "JP1_17") (pinfunction "GPIO_012_JP1_17") (pintype "bidirectional"))
    )
    (net (code "86") (name "unconnected-(U2A-GPIO_013-PadJP1_18)") (class "Default")
      (node (ref "U2") (pin "JP1_18") (pinfunction "GPIO_013_JP1_18") (pintype "bidirectional"))
    )
    (net (code "87") (name "unconnected-(U2A-GPIO_014-PadJP1_19)") (class "Default")
      (node (ref "U2") (pin "JP1_19") (pinfunction "GPIO_014_JP1_19") (pintype "bidirectional"))
    )
    (net (code "88") (name "unconnected-(U2A-GPIO_015-PadJP1_20)") (class "Default")
      (node (ref "U2") (pin "JP1_20") (pinfunction "GPIO_015_JP1_20") (pintype "bidirectional"))
    )
    (net (code "89") (name "unconnected-(U2A-GPIO_016-PadJP1_21)") (class "Default")
      (node (ref "U2") (pin "JP1_21") (pinfunction "GPIO_016_JP1_21") (pintype "bidirectional"))
    )
    (net (code "90") (name "unconnected-(U2A-GPIO_017-PadJP1_22)") (class "Default")
      (node (ref "U2") (pin "JP1_22") (pinfunction "GPIO_017_JP1_22") (pintype "bidirectional"))
    )
    (net (code "91") (name "unconnected-(U2A-GPIO_018-PadJP1_23)") (class "Default")
      (node (ref "U2") (pin "JP1_23") (pinfunction "GPIO_018_JP1_23") (pintype "bidirectional"))
    )
    (net (code "92") (name "unconnected-(U2A-GPIO_019-PadJP1_24)") (class "Default")
      (node (ref "U2") (pin "JP1_24") (pinfunction "GPIO_019_JP1_24") (pintype "bidirectional"))
    )
    (net (code "93") (name "unconnected-(U2A-GPIO_020-PadJP1_25)") (class "Default")
      (node (ref "U2") (pin "JP1_25") (pinfunction "GPIO_020_JP1_25") (pintype "bidirectional"))
    )
    (net (code "94") (name "unconnected-(U2A-GPIO_022-PadJP1_27)") (class "Default")
      (node (ref "U2") (pin "JP1_27") (pinfunction "GPIO_022_JP1_27") (pintype "bidirectional"))
    )
    (net (code "95") (name "unconnected-(U2A-GPIO_024-PadJP1_31)") (class "Default")
      (node (ref "U2") (pin "JP1_31") (pinfunction "GPIO_024_JP1_31") (pintype "bidirectional"))
    )
    (net (code "96") (name "unconnected-(U2A-GPIO_026-PadJP1_33)") (class "Default")
      (node (ref "U2") (pin "JP1_33") (pinfunction "GPIO_026_JP1_33") (pintype "bidirectional"))
    )
    (net (code "97") (name "unconnected-(U2A-GPIO_028-PadJP1_35)") (class "Default")
      (node (ref "U2") (pin "JP1_35") (pinfunction "GPIO_028_JP1_35") (pintype "bidirectional"))
    )
    (net (code "98") (name "unconnected-(U2A-GPIO_029-PadJP1_36)") (class "Default")
      (node (ref "U2") (pin "JP1_36") (pinfunction "GPIO_029_JP1_36") (pintype "bidirectional"))
    )
    (net (code "99") (name "unconnected-(U2A-GPIO_030-PadJP1_37)") (class "Default")
      (node (ref "U2") (pin "JP1_37") (pinfunction "GPIO_030_JP1_37") (pintype "bidirectional"))
    )
    (net (code "100") (name "unconnected-(U2A-GPIO_031-PadJP1_38)") (class "Default")
      (node (ref "U2") (pin "JP1_38") (pinfunction "GPIO_031_JP1_38") (pintype "bidirectional"))
    )
    (net (code "101") (name "unconnected-(U2A-GPIO_032-PadJP1_39)") (class "Default")
      (node (ref "U2") (pin "JP1_39") (pinfunction "GPIO_032_JP1_39") (pintype "bidirectional"))
    )
    (net (code "102") (name "unconnected-(U2A-GPIO_033-PadJP1_40)") (class "Default")
      (node (ref "U2") (pin "JP1_40") (pinfunction "GPIO_033_JP1_40") (pintype "bidirectional"))
    )
    (net (code "103") (name "unconnected-(U2A-SHIELD-PadS1)") (class "Default")
      (node (ref "U2") (pin "S1") (pinfunction "SHIELD_S1") (pintype "passive"))
    )
    (net (code "104") (name "unconnected-(U2A-SHIELD-PadS2)") (class "Default")
      (node (ref "U2") (pin "S2") (pinfunction "SHIELD_S2") (pintype "passive"))
    )
    (net (code "105") (name "unconnected-(U2A-SHIELD-PadS3)") (class "Default")
      (node (ref "U2") (pin "S3") (pinfunction "SHIELD_S3") (pintype "passive"))
    )
    (net (code "106") (name "unconnected-(U2A-SHIELD-PadS4)") (class "Default")
      (node (ref "U2") (pin "S4") (pinfunction "SHIELD_S4") (pintype "passive"))
    )
    (net (code "107") (name "unconnected-(U2B-GPIO-1_VCC3P3-PadJP2_29)") (class "Default")
      (node (ref "U2") (pin "JP2_29") (pinfunction "GPIO-1_VCC3P3_JP2_29") (pintype "power_in"))
    )
    (net (code "108") (name "unconnected-(U2B-GPIO_1_IN0-PadJP2_1)") (class "Default")
      (node (ref "U2") (pin "JP2_1") (pinfunction "GPIO_1_IN0_JP2_1") (pintype "bidirectional"))
    )
    (net (code "109") (name "unconnected-(U2B-GPIO_10-PadJP2_2)") (class "Default")
      (node (ref "U2") (pin "JP2_2") (pinfunction "GPIO_10_JP2_2") (pintype "bidirectional"))
    )
    (net (code "110") (name "unconnected-(U2B-GPIO_11-PadJP2_4)") (class "Default")
      (node (ref "U2") (pin "JP2_4") (pinfunction "GPIO_11_JP2_4") (pintype "bidirectional"))
    )
    (net (code "111") (name "unconnected-(U2B-GPIO_12-PadJP2_5)") (class "Default")
      (node (ref "U2") (pin "JP2_5") (pinfunction "GPIO_12_JP2_5") (pintype "bidirectional"))
    )
    (net (code "112") (name "unconnected-(U2B-GPIO_13-PadJP2_6)") (class "Default")
      (node (ref "U2") (pin "JP2_6") (pinfunction "GPIO_13_JP2_6") (pintype "bidirectional"))
    )
    (net (code "113") (name "unconnected-(U2B-GPIO_15-PadJP2_8)") (class "Default")
      (node (ref "U2") (pin "JP2_8") (pinfunction "GPIO_15_JP2_8") (pintype "bidirectional"))
    )
    (net (code "114") (name "unconnected-(U2B-GPIO_17-PadJP2_10)") (class "Default")
      (node (ref "U2") (pin "JP2_10") (pinfunction "GPIO_17_JP2_10") (pintype "bidirectional"))
    )
    (net (code "115") (name "unconnected-(U2B-GPIO_18-PadJP2_13)") (class "Default")
      (node (ref "U2") (pin "JP2_13") (pinfunction "GPIO_18_JP2_13") (pintype "bidirectional"))
    )
    (net (code "116") (name "unconnected-(U2B-GPIO_110-PadJP2_15)") (class "Default")
      (node (ref "U2") (pin "JP2_15") (pinfunction "GPIO_110_JP2_15") (pintype "bidirectional"))
    )
    (net (code "117") (name "unconnected-(U2B-GPIO_111-PadJP2_16)") (class "Default")
      (node (ref "U2") (pin "JP2_16") (pinfunction "GPIO_111_JP2_16") (pintype "bidirectional"))
    )
    (net (code "118") (name "unconnected-(U2B-GPIO_112-PadJP2_17)") (class "Default")
      (node (ref "U2") (pin "JP2_17") (pinfunction "GPIO_112_JP2_17") (pintype "bidirectional"))
    )
    (net (code "119") (name "unconnected-(U2B-GPIO_113-PadJP2_18)") (class "Default")
      (node (ref "U2") (pin "JP2_18") (pinfunction "GPIO_113_JP2_18") (pintype "bidirectional"))
    )
    (net (code "120") (name "unconnected-(U2B-GPIO_114-PadJP2_19)") (class "Default")
      (node (ref "U2") (pin "JP2_19") (pinfunction "GPIO_114_JP2_19") (pintype "bidirectional"))
    )
    (net (code "121") (name "unconnected-(U2B-GPIO_115-PadJP2_20)") (class "Default")
      (node (ref "U2") (pin "JP2_20") (pinfunction "GPIO_115_JP2_20") (pintype "bidirectional"))
    )
    (net (code "122") (name "unconnected-(U2B-GPIO_116-PadJP2_21)") (class "Default")
      (node (ref "U2") (pin "JP2_21") (pinfunction "GPIO_116_JP2_21") (pintype "bidirectional"))
    )
    (net (code "123") (name "unconnected-(U2B-GPIO_117-PadJP2_22)") (class "Default")
      (node (ref "U2") (pin "JP2_22") (pinfunction "GPIO_117_JP2_22") (pintype "bidirectional"))
    )
    (net (code "124") (name "unconnected-(U2B-GPIO_118-PadJP2_23)") (class "Default")
      (node (ref "U2") (pin "JP2_23") (pinfunction "GPIO_118_JP2_23") (pintype "bidirectional"))
    )
    (net (code "125") (name "unconnected-(U2B-GPIO_119-PadJP2_24)") (class "Default")
      (node (ref "U2") (pin "JP2_24") (pinfunction "GPIO_119_JP2_24") (pintype "bidirectional"))
    )
    (net (code "126") (name "unconnected-(U2B-GPIO_120-PadJP2_25)") (class "Default")
      (node (ref "U2") (pin "JP2_25") (pinfunction "GPIO_120_JP2_25") (pintype "bidirectional"))
    )
    (net (code "127") (name "unconnected-(U2B-GPIO_121-PadJP2_26)") (class "Default")
      (node (ref "U2") (pin "JP2_26") (pinfunction "GPIO_121_JP2_26") (pintype "bidirectional"))
    )
    (net (code "128") (name "unconnected-(U2B-GPIO_122-PadJP2_27)") (class "Default")
      (node (ref "U2") (pin "JP2_27") (pinfunction "GPIO_122_JP2_27") (pintype "bidirectional"))
    )
    (net (code "129") (name "unconnected-(U2B-GPIO_123-PadJP2_28)") (class "Default")
      (node (ref "U2") (pin "JP2_28") (pinfunction "GPIO_123_JP2_28") (pintype "bidirectional"))
    )
    (net (code "130") (name "unconnected-(U2B-GPIO_124-PadJP2_31)") (class "Default")
      (node (ref "U2") (pin "JP2_31") (pinfunction "GPIO_124_JP2_31") (pintype "bidirectional"))
    )
    (net (code "131") (name "unconnected-(U2B-GPIO_125-PadJP2_32)") (class "Default")
      (node (ref "U2") (pin "JP2_32") (pinfunction "GPIO_125_JP2_32") (pintype "bidirectional"))
    )
    (net (code "132") (name "unconnected-(U2B-GPIO_126-PadJP2_33)") (class "Default")
      (node (ref "U2") (pin "JP2_33") (pinfunction "GPIO_126_JP2_33") (pintype "bidirectional"))
    )
    (net (code "133") (name "unconnected-(U2B-GPIO_127-PadJP2_34)") (class "Default")
      (node (ref "U2") (pin "JP2_34") (pinfunction "GPIO_127_JP2_34") (pintype "bidirectional"))
    )
    (net (code "134") (name "unconnected-(U2B-GPIO_128-PadJP2_35)") (class "Default")
      (node (ref "U2") (pin "JP2_35") (pinfunction "GPIO_128_JP2_35") (pintype "bidirectional"))
    )
    (net (code "135") (name "unconnected-(U2B-GPIO_129-PadJP2_36)") (class "Default")
      (node (ref "U2") (pin "JP2_36") (pinfunction "GPIO_129_JP2_36") (pintype "bidirectional"))
    )
    (net (code "136") (name "unconnected-(U2B-GPIO_130-PadJP2_37)") (class "Default")
      (node (ref "U2") (pin "JP2_37") (pinfunction "GPIO_130_JP2_37") (pintype "bidirectional"))
    )
    (net (code "137") (name "unconnected-(U2B-GPIO_131-PadJP2_38)") (class "Default")
      (node (ref "U2") (pin "JP2_38") (pinfunction "GPIO_131_JP2_38") (pintype "bidirectional"))
    )
    (net (code "138") (name "unconnected-(U2B-GPIO_132-PadJP2_39)") (class "Default")
      (node (ref "U2") (pin "JP2_39") (pinfunction "GPIO_132_JP2_39") (pintype "bidirectional"))
    )
    (net (code "139") (name "unconnected-(U2B-GPIO_133-PadJP2_40)") (class "Default")
      (node (ref "U2") (pin "JP2_40") (pinfunction "GPIO_133_JP2_40") (pintype "bidirectional"))
    )
  )
)
